# garden_logger.net
KiCad netlist of a schematic drawn in EAGLE
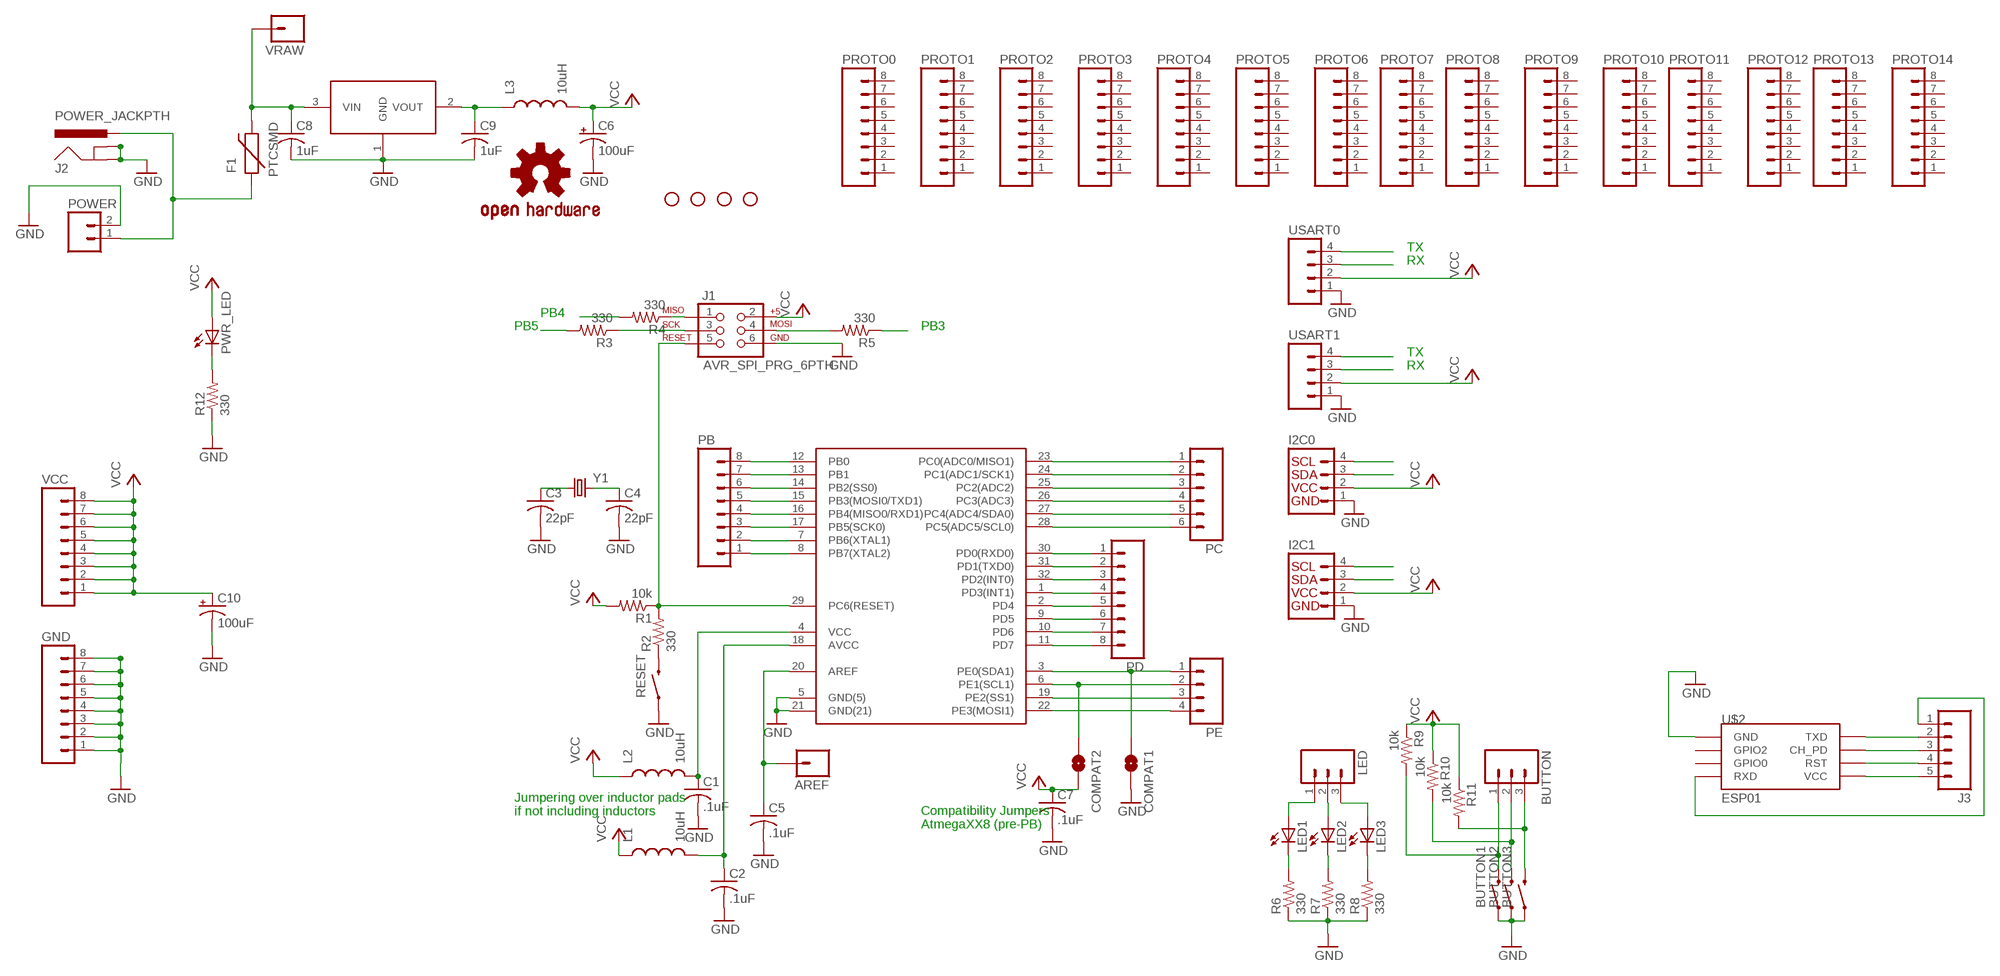
[diagram p0: schematic, sheet 1]

(export (version "E")
  (design (tool "Eeschema 10.0.6"))
  (components
    (comp (ref "AREF")
      (value "M01PTH")
      (footprint "eagle-import:1X01")
      (libsource (lib "eagle-import") (part "M01PTH"))
    )
    (comp (ref "BUTTON")
      (value "M03PTH")
      (footprint "eagle-import:1X03")
      (libsource (lib "eagle-import") (part "M03PTH"))
    )
    (comp (ref "BUTTON1")
      (value "SWITCH-MOMENTARY-2PTH")
      (footprint "eagle-import:TACTILE-PTH")
      (libsource (lib "eagle-import") (part "SWITCH-MOMENTARY-2PTH"))
    )
    (comp (ref "BUTTON2")
      (value "SWITCH-MOMENTARY-2PTH")
      (footprint "eagle-import:TACTILE-PTH")
      (libsource (lib "eagle-import") (part "SWITCH-MOMENTARY-2PTH"))
    )
    (comp (ref "BUTTON3")
      (value "SWITCH-MOMENTARY-2PTH")
      (footprint "eagle-import:TACTILE-PTH")
      (libsource (lib "eagle-import") (part "SWITCH-MOMENTARY-2PTH"))
    )
    (comp (ref "C1")
      (value ".1uF")
      (footprint "eagle-import:C0805")
      (libsource (lib "eagle-import") (part "C-USC0805"))
    )
    (comp (ref "C2")
      (value ".1uF")
      (footprint "eagle-import:C0805")
      (libsource (lib "eagle-import") (part "C-USC0805"))
    )
    (comp (ref "C3")
      (value "22pF")
      (footprint "eagle-import:C0805")
      (libsource (lib "eagle-import") (part "C-USC0805"))
    )
    (comp (ref "C4")
      (value "22pF")
      (footprint "eagle-import:C0805")
      (libsource (lib "eagle-import") (part "C-USC0805"))
    )
    (comp (ref "C5")
      (value ".1uF")
      (footprint "eagle-import:C0805")
      (libsource (lib "eagle-import") (part "C-USC0805"))
    )
    (comp (ref "C6")
      (value "100uF")
      (footprint "eagle-import:CPOL-RADIAL-100UF-25V")
      (libsource (lib "eagle-import") (part "CAP_POLPTH1"))
    )
    (comp (ref "C7")
      (value ".1uF")
      (footprint "eagle-import:C0805")
      (libsource (lib "eagle-import") (part "C-USC0805"))
    )
    (comp (ref "C8")
      (value "1uF")
      (footprint "eagle-import:C0805")
      (libsource (lib "eagle-import") (part "C-USC0805"))
    )
    (comp (ref "C9")
      (value "1uF")
      (footprint "eagle-import:C0805")
      (libsource (lib "eagle-import") (part "C-USC0805"))
    )
    (comp (ref "C10")
      (value "100uF")
      (footprint "eagle-import:CPOL-RADIAL-100UF-25V")
      (libsource (lib "eagle-import") (part "CAP_POLPTH1"))
    )
    (comp (ref "COMPAT1")
      (value "SOLDERJUMPER-OLDNO")
      (footprint "eagle-import:SJ_2S-NO")
      (libsource (lib "eagle-import") (part "SOLDERJUMPER-OLDNO"))
    )
    (comp (ref "COMPAT2")
      (value "SOLDERJUMPER-OLDNO")
      (footprint "eagle-import:SJ_2S-NO")
      (libsource (lib "eagle-import") (part "SOLDERJUMPER-OLDNO"))
    )
    (comp (ref "F1")
      (value "PTCSMD")
      (footprint "eagle-import:PTC-1206")
      (libsource (lib "eagle-import") (part "PTCSMD"))
    )
    (comp (ref "GND")
      (value "M08")
      (footprint "eagle-import:1X08_ROUND")
      (libsource (lib "eagle-import") (part "M08"))
    )
    (comp (ref "H1")
      (value "STAND-OFF")
      (footprint "eagle-import:STAND-OFF")
      (libsource (lib "eagle-import") (part "STAND-OFF"))
    )
    (comp (ref "H2")
      (value "STAND-OFF")
      (footprint "eagle-import:STAND-OFF")
      (libsource (lib "eagle-import") (part "STAND-OFF"))
    )
    (comp (ref "H3")
      (value "STAND-OFF")
      (footprint "eagle-import:STAND-OFF")
      (libsource (lib "eagle-import") (part "STAND-OFF"))
    )
    (comp (ref "H4")
      (value "STAND-OFF")
      (footprint "eagle-import:STAND-OFF")
      (libsource (lib "eagle-import") (part "STAND-OFF"))
    )
    (comp (ref "I2C0")
      (value "I2C_STANDARD")
      (footprint "eagle-import:1X04")
      (libsource (lib "eagle-import") (part "I2C_STANDARD"))
    )
    (comp (ref "I2C1")
      (value "I2C_STANDARD")
      (footprint "eagle-import:1X04")
      (libsource (lib "eagle-import") (part "I2C_STANDARD"))
    )
    (comp (ref "J1")
      (value "AVR_SPI_PRG_6PTH")
      (footprint "eagle-import:2X3")
      (libsource (lib "eagle-import") (part "AVR_SPI_PRG_6PTH"))
    )
    (comp (ref "J2")
      (value "POWER_JACKPTH")
      (footprint "eagle-import:POWER_JACK_PTH")
      (libsource (lib "eagle-import") (part "POWER_JACKPTH"))
    )
    (comp (ref "J3")
      (value "M05PTH")
      (footprint "eagle-import:1X05")
      (libsource (lib "eagle-import") (part "M05PTH"))
    )
    (comp (ref "L1")
      (value "10uH")
      (footprint "eagle-import:0805")
      (libsource (lib "eagle-import") (part "INDUCTOR0805"))
    )
    (comp (ref "L2")
      (value "10uH")
      (footprint "eagle-import:0805")
      (libsource (lib "eagle-import") (part "INDUCTOR0805"))
    )
    (comp (ref "L3")
      (value "10uH")
      (footprint "eagle-import:0805")
      (libsource (lib "eagle-import") (part "INDUCTOR0805"))
    )
    (comp (ref "LED")
      (value "M03PTH")
      (footprint "eagle-import:1X03")
      (libsource (lib "eagle-import") (part "M03PTH"))
    )
    (comp (ref "LED1")
      (value "LEDCHIPLED_0805")
      (footprint "eagle-import:CHIPLED_0805")
      (libsource (lib "eagle-import") (part "LEDCHIPLED_0805"))
    )
    (comp (ref "LED2")
      (value "LEDCHIPLED_0805")
      (footprint "eagle-import:CHIPLED_0805")
      (libsource (lib "eagle-import") (part "LEDCHIPLED_0805"))
    )
    (comp (ref "LED3")
      (value "LEDCHIPLED_0805")
      (footprint "eagle-import:CHIPLED_0805")
      (libsource (lib "eagle-import") (part "LEDCHIPLED_0805"))
    )
    (comp (ref "LOGO1")
      (value "OSHW-LOGOS")
      (footprint "eagle-import:OSHW-LOGO-S")
      (libsource (lib "eagle-import") (part "OSHW-LOGOS"))
    )
    (comp (ref "PB")
      (value "M08")
      (footprint "eagle-import:1X08_ROUND")
      (libsource (lib "eagle-import") (part "M08"))
    )
    (comp (ref "PC")
      (value "M06SILK_FEMALE_PTH")
      (footprint "eagle-import:1X06")
      (libsource (lib "eagle-import") (part "M06SILK_FEMALE_PTH"))
    )
    (comp (ref "PD")
      (value "M08")
      (footprint "eagle-import:1X08_ROUND")
      (libsource (lib "eagle-import") (part "M08"))
    )
    (comp (ref "PE")
      (value "M04PTH")
      (footprint "eagle-import:1X04")
      (libsource (lib "eagle-import") (part "M04PTH"))
    )
    (comp (ref "POWER")
      (value "M02PTH")
      (footprint "eagle-import:1X02")
      (libsource (lib "eagle-import") (part "M02PTH"))
    )
    (comp (ref "PROTO0")
      (value "M08")
      (footprint "eagle-import:1X08_ROUND")
      (libsource (lib "eagle-import") (part "M08"))
    )
    (comp (ref "PROTO1")
      (value "M08")
      (footprint "eagle-import:1X08_ROUND")
      (libsource (lib "eagle-import") (part "M08"))
    )
    (comp (ref "PROTO2")
      (value "M08")
      (footprint "eagle-import:1X08_ROUND")
      (libsource (lib "eagle-import") (part "M08"))
    )
    (comp (ref "PROTO3")
      (value "M08")
      (footprint "eagle-import:1X08_ROUND")
      (libsource (lib "eagle-import") (part "M08"))
    )
    (comp (ref "PROTO4")
      (value "M08")
      (footprint "eagle-import:1X08_ROUND")
      (libsource (lib "eagle-import") (part "M08"))
    )
    (comp (ref "PROTO5")
      (value "M08")
      (footprint "eagle-import:1X08_ROUND")
      (libsource (lib "eagle-import") (part "M08"))
    )
    (comp (ref "PROTO6")
      (value "M08")
      (footprint "eagle-import:1X08_ROUND")
      (libsource (lib "eagle-import") (part "M08"))
    )
    (comp (ref "PROTO7")
      (value "M08")
      (footprint "eagle-import:1X08_ROUND")
      (libsource (lib "eagle-import") (part "M08"))
    )
    (comp (ref "PROTO8")
      (value "M08")
      (footprint "eagle-import:1X08_ROUND")
      (libsource (lib "eagle-import") (part "M08"))
    )
    (comp (ref "PROTO9")
      (value "M08")
      (footprint "eagle-import:1X08_ROUND")
      (libsource (lib "eagle-import") (part "M08"))
    )
    (comp (ref "PROTO10")
      (value "M08")
      (footprint "eagle-import:1X08_ROUND")
      (libsource (lib "eagle-import") (part "M08"))
    )
    (comp (ref "PROTO11")
      (value "M08")
      (footprint "eagle-import:1X08_ROUND")
      (libsource (lib "eagle-import") (part "M08"))
    )
    (comp (ref "PROTO12")
      (value "M08")
      (footprint "eagle-import:1X08_ROUND")
      (libsource (lib "eagle-import") (part "M08"))
    )
    (comp (ref "PROTO13")
      (value "M08")
      (footprint "eagle-import:1X08_ROUND")
      (libsource (lib "eagle-import") (part "M08"))
    )
    (comp (ref "PROTO14")
      (value "M08")
      (footprint "eagle-import:1X08_ROUND")
      (libsource (lib "eagle-import") (part "M08"))
    )
    (comp (ref "PWR_LED")
      (value "LEDCHIPLED_0805")
      (footprint "eagle-import:CHIPLED_0805")
      (libsource (lib "eagle-import") (part "LEDCHIPLED_0805"))
    )
    (comp (ref "R1")
      (value "10k")
      (footprint "eagle-import:R0805")
      (libsource (lib "eagle-import") (part "R-US_R0805"))
    )
    (comp (ref "R2")
      (value "330")
      (footprint "eagle-import:R0805")
      (libsource (lib "eagle-import") (part "R-US_R0805"))
    )
    (comp (ref "R3")
      (value "330")
      (footprint "eagle-import:R0805")
      (libsource (lib "eagle-import") (part "R-US_R0805"))
    )
    (comp (ref "R4")
      (value "330")
      (footprint "eagle-import:R0805")
      (libsource (lib "eagle-import") (part "R-US_R0805"))
    )
    (comp (ref "R5")
      (value "330")
      (footprint "eagle-import:R0805")
      (libsource (lib "eagle-import") (part "R-US_R0805"))
    )
    (comp (ref "R6")
      (value "330")
      (footprint "eagle-import:R0805")
      (libsource (lib "eagle-import") (part "R-US_R0805"))
    )
    (comp (ref "R7")
      (value "330")
      (footprint "eagle-import:R0805")
      (libsource (lib "eagle-import") (part "R-US_R0805"))
    )
    (comp (ref "R8")
      (value "330")
      (footprint "eagle-import:R0805")
      (libsource (lib "eagle-import") (part "R-US_R0805"))
    )
    (comp (ref "R9")
      (value "10k")
      (footprint "eagle-import:R0805")
      (libsource (lib "eagle-import") (part "R-US_R0805"))
    )
    (comp (ref "R10")
      (value "10k")
      (footprint "eagle-import:R0805")
      (libsource (lib "eagle-import") (part "R-US_R0805"))
    )
    (comp (ref "R11")
      (value "10k")
      (footprint "eagle-import:R0805")
      (libsource (lib "eagle-import") (part "R-US_R0805"))
    )
    (comp (ref "R12")
      (value "330")
      (footprint "eagle-import:R0805")
      (libsource (lib "eagle-import") (part "R-US_R0805"))
    )
    (comp (ref "RESET")
      (value "SWITCH-MOMENTARY-2PTH")
      (footprint "eagle-import:TACTILE-PTH")
      (libsource (lib "eagle-import") (part "SWITCH-MOMENTARY-2PTH"))
    )
    (comp (ref "U$1")
      (value "ATMEGA328PB_TQFP")
      (footprint "eagle-import:TQFP32-08")
      (libsource (lib "eagle-import") (part "ATMEGA328PB_TQFP"))
    )
    (comp (ref "U$2")
      (value "ESP01")
      (footprint "eagle-import:ESP01")
      (libsource (lib "eagle-import") (part "ESP01"))
    )
    (comp (ref "U$3")
      (value "MCP1702")
      (footprint "eagle-import:SOT23-3")
      (libsource (lib "eagle-import") (part "MCP1702"))
    )
    (comp (ref "USART0")
      (value "M04PTH")
      (footprint "eagle-import:1X04")
      (libsource (lib "eagle-import") (part "M04PTH"))
    )
    (comp (ref "USART1")
      (value "M04PTH")
      (footprint "eagle-import:1X04")
      (libsource (lib "eagle-import") (part "M04PTH"))
    )
    (comp (ref "VCC")
      (value "M08")
      (footprint "eagle-import:1X08_ROUND")
      (libsource (lib "eagle-import") (part "M08"))
    )
    (comp (ref "VRAW")
      (value "M01PTH")
      (footprint "eagle-import:1X01")
      (libsource (lib "eagle-import") (part "M01PTH"))
    )
    (comp (ref "Y1")
      (value "CRYSTALHC49US")
      (footprint "eagle-import:HC49US")
      (libsource (lib "eagle-import") (part "CRYSTALHC49US"))
    )
  )
  (nets
    (net (code "1") (name "/PB3") (class "Default")
      (node (ref "PB") (pin "5") (pinfunction "5_5") (pintype "passive"))
      (node (ref "R5") (pin "1") (pinfunction "1_1") (pintype "passive"))
      (node (ref "U$1") (pin "15") (pinfunction "PB3(MOSI0/TXD1)_15") (pintype "bidirectional"))
      (node (ref "USART1") (pin "4") (pinfunction "4_4") (pintype "passive"))
    )
    (net (code "2") (name "/PB4") (class "Default")
      (node (ref "PB") (pin "4") (pinfunction "4_4") (pintype "passive"))
      (node (ref "R4") (pin "2") (pinfunction "2_2") (pintype "passive"))
      (node (ref "U$1") (pin "16") (pinfunction "PB4(MISO0/RXD1)_16") (pintype "bidirectional"))
      (node (ref "USART1") (pin "3") (pinfunction "3_3") (pintype "passive"))
    )
    (net (code "3") (name "/PB5") (class "Default")
      (node (ref "PB") (pin "3") (pinfunction "3_3") (pintype "passive"))
      (node (ref "R3") (pin "2") (pinfunction "2_2") (pintype "passive"))
      (node (ref "U$1") (pin "17") (pinfunction "PB5(SCK0)_17") (pintype "bidirectional"))
    )
    (net (code "4") (name "/PB6") (class "Default")
      (node (ref "C3") (pin "1") (pinfunction "1_1") (pintype "passive"))
      (node (ref "PB") (pin "2") (pinfunction "2_2") (pintype "passive"))
      (node (ref "U$1") (pin "7") (pinfunction "PB6(XTAL1)_7") (pintype "bidirectional"))
      (node (ref "Y1") (pin "1") (pinfunction "1_1") (pintype "passive"))
    )
    (net (code "5") (name "/PB7") (class "Default")
      (node (ref "C4") (pin "1") (pinfunction "1_1") (pintype "passive"))
      (node (ref "PB") (pin "1") (pinfunction "1_1") (pintype "passive"))
      (node (ref "U$1") (pin "8") (pinfunction "PB7(XTAL2)_8") (pintype "bidirectional"))
      (node (ref "Y1") (pin "2") (pinfunction "2_2") (pintype "passive"))
    )
    (net (code "6") (name "/PC4") (class "Default")
      (node (ref "I2C0") (pin "3") (pinfunction "3_3") (pintype "passive"))
      (node (ref "PC") (pin "5") (pinfunction "5_5") (pintype "passive"))
      (node (ref "U$1") (pin "27") (pinfunction "PC4(ADC4/SDA0)_27") (pintype "bidirectional"))
    )
    (net (code "7") (name "/PC5") (class "Default")
      (node (ref "I2C0") (pin "4") (pinfunction "4_4") (pintype "passive"))
      (node (ref "PC") (pin "6") (pinfunction "6_6") (pintype "passive"))
      (node (ref "U$1") (pin "28") (pinfunction "PC5(ADC5/SCL0)_28") (pintype "bidirectional"))
    )
    (net (code "8") (name "/PD0") (class "Default")
      (node (ref "PD") (pin "1") (pinfunction "1_1") (pintype "passive"))
      (node (ref "U$1") (pin "30") (pinfunction "PD0(RXD0)_30") (pintype "bidirectional"))
      (node (ref "USART0") (pin "3") (pinfunction "3_3") (pintype "passive"))
    )
    (net (code "9") (name "/PD1") (class "Default")
      (node (ref "PD") (pin "2") (pinfunction "2_2") (pintype "passive"))
      (node (ref "U$1") (pin "31") (pinfunction "PD1(TXD0)_31") (pintype "bidirectional"))
      (node (ref "USART0") (pin "4") (pinfunction "4_4") (pintype "passive"))
    )
    (net (code "10") (name "/PE0") (class "Default")
      (node (ref "COMPAT1") (pin "1") (pinfunction "1_1") (pintype "passive"))
      (node (ref "I2C1") (pin "3") (pinfunction "3_3") (pintype "passive"))
      (node (ref "PE") (pin "1") (pinfunction "1_1") (pintype "passive"))
      (node (ref "U$1") (pin "3") (pinfunction "PE0(SDA1)_3") (pintype "bidirectional"))
    )
    (net (code "11") (name "/PE1") (class "Default")
      (node (ref "COMPAT2") (pin "1") (pinfunction "1_1") (pintype "passive"))
      (node (ref "I2C1") (pin "4") (pinfunction "4_4") (pintype "passive"))
      (node (ref "PE") (pin "2") (pinfunction "2_2") (pintype "passive"))
      (node (ref "U$1") (pin "6") (pinfunction "PE1(SCL1)_6") (pintype "bidirectional"))
    )
    (net (code "12") (name "GND") (class "Default")
      (node (ref "BUTTON1") (pin "1") (pinfunction "1_1") (pintype "passive"))
      (node (ref "BUTTON2") (pin "1") (pinfunction "1_1") (pintype "passive"))
      (node (ref "BUTTON3") (pin "1") (pinfunction "1_1") (pintype "passive"))
      (node (ref "C1") (pin "2") (pinfunction "2_2") (pintype "passive"))
      (node (ref "C10") (pin "2") (pinfunction "-_2") (pintype "passive"))
      (node (ref "C2") (pin "2") (pinfunction "2_2") (pintype "passive"))
      (node (ref "C3") (pin "2") (pinfunction "2_2") (pintype "passive"))
      (node (ref "C4") (pin "2") (pinfunction "2_2") (pintype "passive"))
      (node (ref "C5") (pin "2") (pinfunction "2_2") (pintype "passive"))
      (node (ref "C6") (pin "2") (pinfunction "-_2") (pintype "passive"))
      (node (ref "C7") (pin "2") (pinfunction "2_2") (pintype "passive"))
      (node (ref "C8") (pin "2") (pinfunction "2_2") (pintype "passive"))
      (node (ref "C9") (pin "2") (pinfunction "2_2") (pintype "passive"))
      (node (ref "COMPAT1") (pin "2") (pinfunction "2_2") (pintype "passive"))
      (node (ref "GND") (pin "1") (pinfunction "1_1") (pintype "passive"))
      (node (ref "GND") (pin "2") (pinfunction "2_2") (pintype "passive"))
      (node (ref "GND") (pin "3") (pinfunction "3_3") (pintype "passive"))
      (node (ref "GND") (pin "4") (pinfunction "4_4") (pintype "passive"))
      (node (ref "GND") (pin "5") (pinfunction "5_5") (pintype "passive"))
      (node (ref "GND") (pin "6") (pinfunction "6_6") (pintype "passive"))
      (node (ref "GND") (pin "7") (pinfunction "7_7") (pintype "passive"))
      (node (ref "GND") (pin "8") (pinfunction "8_8") (pintype "passive"))
      (node (ref "I2C0") (pin "1") (pinfunction "1_1") (pintype "passive"))
      (node (ref "I2C1") (pin "1") (pinfunction "1_1") (pintype "passive"))
      (node (ref "J1") (pin "6") (pinfunction "6_6") (pintype "passive"))
      (node (ref "J2") (pin "GND") (pinfunction "GND_GND") (pintype "bidirectional"))
      (node (ref "J2") (pin "GNDBREAK") (pinfunction "GNDBREAK_GNDBREAK") (pintype "bidirectional"))
      (node (ref "POWER") (pin "2") (pinfunction "2_2") (pintype "passive"))
      (node (ref "R12") (pin "1") (pinfunction "1_1") (pintype "passive"))
      (node (ref "R6") (pin "1") (pinfunction "1_1") (pintype "passive"))
      (node (ref "R7") (pin "1") (pinfunction "1_1") (pintype "passive"))
      (node (ref "R8") (pin "1") (pinfunction "1_1") (pintype "passive"))
      (node (ref "RESET") (pin "1") (pinfunction "1_1") (pintype "passive"))
      (node (ref "U$1") (pin "21") (pinfunction "GND(21)_21") (pintype "power_in"))
      (node (ref "U$1") (pin "5") (pinfunction "GND(5)_5") (pintype "power_in"))
      (node (ref "U$2") (pin "GND") (pinfunction "GND_GND") (pintype "bidirectional"))
      (node (ref "U$3") (pin "1") (pinfunction "GND_1") (pintype "bidirectional"))
      (node (ref "USART0") (pin "1") (pinfunction "1_1") (pintype "passive"))
      (node (ref "USART1") (pin "1") (pinfunction "1_1") (pintype "passive"))
    )
    (net (code "13") (name "Net-(BUTTON1-2)") (class "Default")
      (node (ref "BUTTON") (pin "1") (pinfunction "1_1") (pintype "passive"))
      (node (ref "BUTTON1") (pin "3") (pinfunction "2_3") (pintype "passive"))
      (node (ref "R9") (pin "2") (pinfunction "2_2") (pintype "passive"))
    )
    (net (code "14") (name "Net-(BUTTON2-2)") (class "Default")
      (node (ref "BUTTON") (pin "2") (pinfunction "2_2") (pintype "passive"))
      (node (ref "BUTTON2") (pin "3") (pinfunction "2_3") (pintype "passive"))
      (node (ref "R10") (pin "2") (pinfunction "2_2") (pintype "passive"))
    )
    (net (code "15") (name "Net-(BUTTON3-2)") (class "Default")
      (node (ref "BUTTON") (pin "3") (pinfunction "3_3") (pintype "passive"))
      (node (ref "BUTTON3") (pin "3") (pinfunction "2_3") (pintype "passive"))
      (node (ref "R11") (pin "2") (pinfunction "2_2") (pintype "passive"))
    )
    (net (code "16") (name "Net-(F1-Pad1)") (class "Default")
      (node (ref "F1") (pin "1") (pinfunction "1_1") (pintype "bidirectional"))
      (node (ref "J2") (pin "PWR") (pinfunction "PWR_PWR") (pintype "bidirectional"))
      (node (ref "POWER") (pin "1") (pinfunction "1_1") (pintype "passive"))
    )
    (net (code "17") (name "Net-(J1-Pad1)") (class "Default")
      (node (ref "J1") (pin "1") (pinfunction "1_1") (pintype "passive"))
      (node (ref "R4") (pin "1") (pinfunction "1_1") (pintype "passive"))
    )
    (net (code "18") (name "Net-(J1-Pad3)") (class "Default")
      (node (ref "J1") (pin "3") (pinfunction "3_3") (pintype "passive"))
      (node (ref "R3") (pin "1") (pinfunction "1_1") (pintype "passive"))
    )
    (net (code "19") (name "Net-(J1-Pad4)") (class "Default")
      (node (ref "J1") (pin "4") (pinfunction "4_4") (pintype "passive"))
      (node (ref "R5") (pin "2") (pinfunction "2_2") (pintype "passive"))
    )
    (net (code "20") (name "Net-(J3-Pad3)") (class "Default")
      (node (ref "J3") (pin "3") (pinfunction "3_3") (pintype "passive"))
      (node (ref "U$2") (pin "CH_PD") (pinfunction "CH_PD_CH_PD") (pintype "bidirectional"))
    )
    (net (code "21") (name "Net-(J3-Pad4)") (class "Default")
      (node (ref "J3") (pin "4") (pinfunction "4_4") (pintype "passive"))
      (node (ref "U$2") (pin "RST") (pinfunction "RST_RST") (pintype "bidirectional"))
    )
    (net (code "22") (name "Net-(J3-Pad5)") (class "Default")
      (node (ref "J3") (pin "5") (pinfunction "5_5") (pintype "passive"))
      (node (ref "U$2") (pin "VCC") (pinfunction "VCC_VCC") (pintype "bidirectional"))
    )
    (net (code "23") (name "Net-(LED-Pad1)") (class "Default")
      (node (ref "LED") (pin "1") (pinfunction "1_1") (pintype "passive"))
      (node (ref "LED1") (pin "A") (pinfunction "A_A") (pintype "passive"))
    )
    (net (code "24") (name "Net-(LED-Pad2)") (class "Default")
      (node (ref "LED") (pin "2") (pinfunction "2_2") (pintype "passive"))
      (node (ref "LED2") (pin "A") (pinfunction "A_A") (pintype "passive"))
    )
    (net (code "25") (name "Net-(LED-Pad3)") (class "Default")
      (node (ref "LED") (pin "3") (pinfunction "3_3") (pintype "passive"))
      (node (ref "LED3") (pin "A") (pinfunction "A_A") (pintype "passive"))
    )
    (net (code "26") (name "Net-(LED1-PadC)") (class "Default")
      (node (ref "LED1") (pin "C") (pinfunction "C_C") (pintype "passive"))
      (node (ref "R6") (pin "2") (pinfunction "2_2") (pintype "passive"))
    )
    (net (code "27") (name "Net-(LED2-PadC)") (class "Default")
      (node (ref "LED2") (pin "C") (pinfunction "C_C") (pintype "passive"))
      (node (ref "R7") (pin "2") (pinfunction "2_2") (pintype "passive"))
    )
    (net (code "28") (name "Net-(LED3-PadC)") (class "Default")
      (node (ref "LED3") (pin "C") (pinfunction "C_C") (pintype "passive"))
      (node (ref "R8") (pin "2") (pinfunction "2_2") (pintype "passive"))
    )
    (net (code "29") (name "Net-(PWR_LED-PadC)") (class "Default")
      (node (ref "PWR_LED") (pin "C") (pinfunction "C_C") (pintype "passive"))
      (node (ref "R12") (pin "2") (pinfunction "2_2") (pintype "passive"))
    )
    (net (code "30") (name "Net-(RESET-2)") (class "Default")
      (node (ref "R2") (pin "1") (pinfunction "1_1") (pintype "passive"))
      (node (ref "RESET") (pin "3") (pinfunction "2_3") (pintype "passive"))
    )
    (net (code "31") (name "Net-(U$1-AREF)") (class "Default")
      (node (ref "AREF") (pin "1") (pinfunction "1_1") (pintype "passive"))
      (node (ref "C5") (pin "1") (pinfunction "1_1") (pintype "passive"))
      (node (ref "U$1") (pin "20") (pinfunction "AREF_20") (pintype "bidirectional"))
    )
    (net (code "32") (name "Net-(U$1-AVCC)") (class "Default")
      (node (ref "C2") (pin "1") (pinfunction "1_1") (pintype "passive"))
      (node (ref "L1") (pin "2") (pinfunction "2_2") (pintype "passive"))
      (node (ref "U$1") (pin "18") (pinfunction "AVCC_18") (pintype "power_in"))
    )
    (net (code "33") (name "Net-(U$1-PB0)") (class "Default")
      (node (ref "PB") (pin "8") (pinfunction "8_8") (pintype "passive"))
      (node (ref "U$1") (pin "12") (pinfunction "PB0_12") (pintype "bidirectional"))
    )
    (net (code "34") (name "Net-(U$1-PB1)") (class "Default")
      (node (ref "PB") (pin "7") (pinfunction "7_7") (pintype "passive"))
      (node (ref "U$1") (pin "13") (pinfunction "PB1_13") (pintype "bidirectional"))
    )
    (net (code "35") (name "Net-(U$1-PB2(SS0))") (class "Default")
      (node (ref "PB") (pin "6") (pinfunction "6_6") (pintype "passive"))
      (node (ref "U$1") (pin "14") (pinfunction "PB2(SS0)_14") (pintype "bidirectional"))
    )
    (net (code "36") (name "Net-(U$1-PC0(ADC0{slash}MISO1))") (class "Default")
      (node (ref "PC") (pin "1") (pinfunction "1_1") (pintype "passive"))
      (node (ref "U$1") (pin "23") (pinfunction "PC0(ADC0/MISO1)_23") (pintype "bidirectional"))
    )
    (net (code "37") (name "Net-(U$1-PC1(ADC1{slash}SCK1))") (class "Default")
      (node (ref "PC") (pin "2") (pinfunction "2_2") (pintype "passive"))
      (node (ref "U$1") (pin "24") (pinfunction "PC1(ADC1/SCK1)_24") (pintype "bidirectional"))
    )
    (net (code "38") (name "Net-(U$1-PC2(ADC2))") (class "Default")
      (node (ref "PC") (pin "3") (pinfunction "3_3") (pintype "passive"))
      (node (ref "U$1") (pin "25") (pinfunction "PC2(ADC2)_25") (pintype "bidirectional"))
    )
    (net (code "39") (name "Net-(U$1-PC3(ADC3))") (class "Default")
      (node (ref "PC") (pin "4") (pinfunction "4_4") (pintype "passive"))
      (node (ref "U$1") (pin "26") (pinfunction "PC3(ADC3)_26") (pintype "bidirectional"))
    )
    (net (code "40") (name "Net-(U$1-PC6(RESET))") (class "Default")
      (node (ref "J1") (pin "5") (pinfunction "5_5") (pintype "passive"))
      (node (ref "R1") (pin "1") (pinfunction "1_1") (pintype "passive"))
      (node (ref "R2") (pin "2") (pinfunction "2_2") (pintype "passive"))
      (node (ref "U$1") (pin "29") (pinfunction "PC6(RESET)_29") (pintype "bidirectional"))
    )
    (net (code "41") (name "Net-(U$1-PD2(INT0))") (class "Default")
      (node (ref "PD") (pin "3") (pinfunction "3_3") (pintype "passive"))
      (node (ref "U$1") (pin "32") (pinfunction "PD2(INT0)_32") (pintype "bidirectional"))
    )
    (net (code "42") (name "Net-(U$1-PD3(INT1))") (class "Default")
      (node (ref "PD") (pin "4") (pinfunction "4_4") (pintype "passive"))
      (node (ref "U$1") (pin "1") (pinfunction "PD3(INT1)_1") (pintype "bidirectional"))
    )
    (net (code "43") (name "Net-(U$1-PD4)") (class "Default")
      (node (ref "PD") (pin "5") (pinfunction "5_5") (pintype "passive"))
      (node (ref "U$1") (pin "2") (pinfunction "PD4_2") (pintype "bidirectional"))
    )
    (net (code "44") (name "Net-(U$1-PD5)") (class "Default")
      (node (ref "PD") (pin "6") (pinfunction "6_6") (pintype "passive"))
      (node (ref "U$1") (pin "9") (pinfunction "PD5_9") (pintype "bidirectional"))
    )
    (net (code "45") (name "Net-(U$1-PD6)") (class "Default")
      (node (ref "PD") (pin "7") (pinfunction "7_7") (pintype "passive"))
      (node (ref "U$1") (pin "10") (pinfunction "PD6_10") (pintype "bidirectional"))
    )
    (net (code "46") (name "Net-(U$1-PD7)") (class "Default")
      (node (ref "PD") (pin "8") (pinfunction "8_8") (pintype "passive"))
      (node (ref "U$1") (pin "11") (pinfunction "PD7_11") (pintype "bidirectional"))
    )
    (net (code "47") (name "Net-(U$1-PE2(SS1))") (class "Default")
      (node (ref "PE") (pin "3") (pinfunction "3_3") (pintype "passive"))
      (node (ref "U$1") (pin "19") (pinfunction "PE2(SS1)_19") (pintype "bidirectional"))
    )
    (net (code "48") (name "Net-(U$1-PE3(MOSI1))") (class "Default")
      (node (ref "PE") (pin "4") (pinfunction "4_4") (pintype "passive"))
      (node (ref "U$1") (pin "22") (pinfunction "PE3(MOSI1)_22") (pintype "bidirectional"))
    )
    (net (code "49") (name "Net-(U$1-VCC)") (class "Default")
      (node (ref "C1") (pin "1") (pinfunction "1_1") (pintype "passive"))
      (node (ref "L2") (pin "2") (pinfunction "2_2") (pintype "passive"))
      (node (ref "U$1") (pin "4") (pinfunction "VCC_4") (pintype "power_in"))
    )
    (net (code "50") (name "Net-(U$2-RXD)") (class "Default")
      (node (ref "J3") (pin "1") (pinfunction "1_1") (pintype "passive"))
      (node (ref "U$2") (pin "RX") (pinfunction "RXD_RX") (pintype "bidirectional"))
    )
    (net (code "51") (name "Net-(U$2-TXD)") (class "Default")
      (node (ref "J3") (pin "2") (pinfunction "2_2") (pintype "passive"))
      (node (ref "U$2") (pin "TX") (pinfunction "TXD_TX") (pintype "bidirectional"))
    )
    (net (code "52") (name "Net-(U$3-VIN)") (class "Default")
      (node (ref "C8") (pin "1") (pinfunction "1_1") (pintype "passive"))
      (node (ref "F1") (pin "2") (pinfunction "2_2") (pintype "bidirectional"))
      (node (ref "U$3") (pin "3") (pinfunction "VIN_3") (pintype "bidirectional"))
      (node (ref "VRAW") (pin "1") (pinfunction "1_1") (pintype "passive"))
    )
    (net (code "53") (name "Net-(U$3-VOUT)") (class "Default")
      (node (ref "C9") (pin "1") (pinfunction "1_1") (pintype "passive"))
      (node (ref "L3") (pin "1") (pinfunction "1_1") (pintype "passive"))
      (node (ref "U$3") (pin "2") (pinfunction "VOUT_2") (pintype "bidirectional"))
    )
    (net (code "54") (name "VCC") (class "Default")
      (node (ref "C10") (pin "1") (pinfunction "+_1") (pintype "passive"))
      (node (ref "C6") (pin "1") (pinfunction "+_1") (pintype "passive"))
      (node (ref "C7") (pin "1") (pinfunction "1_1") (pintype "passive"))
      (node (ref "COMPAT2") (pin "2") (pinfunction "2_2") (pintype "passive"))
      (node (ref "I2C0") (pin "2") (pinfunction "2_2") (pintype "passive"))
      (node (ref "I2C1") (pin "2") (pinfunction "2_2") (pintype "passive"))
      (node (ref "J1") (pin "2") (pinfunction "2_2") (pintype "passive"))
      (node (ref "L1") (pin "1") (pinfunction "1_1") (pintype "passive"))
      (node (ref "L2") (pin "1") (pinfunction "1_1") (pintype "passive"))
      (node (ref "L3") (pin "2") (pinfunction "2_2") (pintype "passive"))
      (node (ref "PWR_LED") (pin "A") (pinfunction "A_A") (pintype "passive"))
      (node (ref "R1") (pin "2") (pinfunction "2_2") (pintype "passive"))
      (node (ref "R10") (pin "1") (pinfunction "1_1") (pintype "passive"))
      (node (ref "R11") (pin "1") (pinfunction "1_1") (pintype "passive"))
      (node (ref "R9") (pin "1") (pinfunction "1_1") (pintype "passive"))
      (node (ref "USART0") (pin "2") (pinfunction "2_2") (pintype "passive"))
      (node (ref "USART1") (pin "2") (pinfunction "2_2") (pintype "passive"))
      (node (ref "VCC") (pin "1") (pinfunction "1_1") (pintype "passive"))
      (node (ref "VCC") (pin "2") (pinfunction "2_2") (pintype "passive"))
      (node (ref "VCC") (pin "3") (pinfunction "3_3") (pintype "passive"))
      (node (ref "VCC") (pin "4") (pinfunction "4_4") (pintype "passive"))
      (node (ref "VCC") (pin "5") (pinfunction "5_5") (pintype "passive"))
      (node (ref "VCC") (pin "6") (pinfunction "6_6") (pintype "passive"))
      (node (ref "VCC") (pin "7") (pinfunction "7_7") (pintype "passive"))
      (node (ref "VCC") (pin "8") (pinfunction "8_8") (pintype "passive"))
    )
    (net (code "55") (name "unconnected-(PROTO0-Pad1)") (class "Default")
      (node (ref "PROTO0") (pin "1") (pinfunction "1_1") (pintype "passive"))
    )
    (net (code "56") (name "unconnected-(PROTO0-Pad2)") (class "Default")
      (node (ref "PROTO0") (pin "2") (pinfunction "2_2") (pintype "passive"))
    )
    (net (code "57") (name "unconnected-(PROTO0-Pad3)") (class "Default")
      (node (ref "PROTO0") (pin "3") (pinfunction "3_3") (pintype "passive"))
    )
    (net (code "58") (name "unconnected-(PROTO0-Pad4)") (class "Default")
      (node (ref "PROTO0") (pin "4") (pinfunction "4_4") (pintype "passive"))
    )
    (net (code "59") (name "unconnected-(PROTO0-Pad5)") (class "Default")
      (node (ref "PROTO0") (pin "5") (pinfunction "5_5") (pintype "passive"))
    )
    (net (code "60") (name "unconnected-(PROTO0-Pad6)") (class "Default")
      (node (ref "PROTO0") (pin "6") (pinfunction "6_6") (pintype "passive"))
    )
    (net (code "61") (name "unconnected-(PROTO0-Pad7)") (class "Default")
      (node (ref "PROTO0") (pin "7") (pinfunction "7_7") (pintype "passive"))
    )
    (net (code "62") (name "unconnected-(PROTO0-Pad8)") (class "Default")
      (node (ref "PROTO0") (pin "8") (pinfunction "8_8") (pintype "passive"))
    )
    (net (code "63") (name "unconnected-(PROTO1-Pad1)") (class "Default")
      (node (ref "PROTO1") (pin "1") (pinfunction "1_1") (pintype "passive"))
    )
    (net (code "64") (name "unconnected-(PROTO1-Pad2)") (class "Default")
      (node (ref "PROTO1") (pin "2") (pinfunction "2_2") (pintype "passive"))
    )
    (net (code "65") (name "unconnected-(PROTO1-Pad3)") (class "Default")
      (node (ref "PROTO1") (pin "3") (pinfunction "3_3") (pintype "passive"))
    )
    (net (code "66") (name "unconnected-(PROTO1-Pad4)") (class "Default")
      (node (ref "PROTO1") (pin "4") (pinfunction "4_4") (pintype "passive"))
    )
    (net (code "67") (name "unconnected-(PROTO1-Pad5)") (class "Default")
      (node (ref "PROTO1") (pin "5") (pinfunction "5_5") (pintype "passive"))
    )
    (net (code "68") (name "unconnected-(PROTO1-Pad6)") (class "Default")
      (node (ref "PROTO1") (pin "6") (pinfunction "6_6") (pintype "passive"))
    )
    (net (code "69") (name "unconnected-(PROTO1-Pad7)") (class "Default")
      (node (ref "PROTO1") (pin "7") (pinfunction "7_7") (pintype "passive"))
    )
    (net (code "70") (name "unconnected-(PROTO1-Pad8)") (class "Default")
      (node (ref "PROTO1") (pin "8") (pinfunction "8_8") (pintype "passive"))
    )
    (net (code "71") (name "unconnected-(PROTO2-Pad1)") (class "Default")
      (node (ref "PROTO2") (pin "1") (pinfunction "1_1") (pintype "passive"))
    )
    (net (code "72") (name "unconnected-(PROTO2-Pad2)") (class "Default")
      (node (ref "PROTO2") (pin "2") (pinfunction "2_2") (pintype "passive"))
    )
    (net (code "73") (name "unconnected-(PROTO2-Pad3)") (class "Default")
      (node (ref "PROTO2") (pin "3") (pinfunction "3_3") (pintype "passive"))
    )
    (net (code "74") (name "unconnected-(PROTO2-Pad4)") (class "Default")
      (node (ref "PROTO2") (pin "4") (pinfunction "4_4") (pintype "passive"))
    )
    (net (code "75") (name "unconnected-(PROTO2-Pad5)") (class "Default")
      (node (ref "PROTO2") (pin "5") (pinfunction "5_5") (pintype "passive"))
    )
    (net (code "76") (name "unconnected-(PROTO2-Pad6)") (class "Default")
      (node (ref "PROTO2") (pin "6") (pinfunction "6_6") (pintype "passive"))
    )
    (net (code "77") (name "unconnected-(PROTO2-Pad7)") (class "Default")
      (node (ref "PROTO2") (pin "7") (pinfunction "7_7") (pintype "passive"))
    )
    (net (code "78") (name "unconnected-(PROTO2-Pad8)") (class "Default")
      (node (ref "PROTO2") (pin "8") (pinfunction "8_8") (pintype "passive"))
    )
    (net (code "79") (name "unconnected-(PROTO3-Pad1)") (class "Default")
      (node (ref "PROTO3") (pin "1") (pinfunction "1_1") (pintype "passive"))
    )
    (net (code "80") (name "unconnected-(PROTO3-Pad2)") (class "Default")
      (node (ref "PROTO3") (pin "2") (pinfunction "2_2") (pintype "passive"))
    )
    (net (code "81") (name "unconnected-(PROTO3-Pad3)") (class "Default")
      (node (ref "PROTO3") (pin "3") (pinfunction "3_3") (pintype "passive"))
    )
    (net (code "82") (name "unconnected-(PROTO3-Pad4)") (class "Default")
      (node (ref "PROTO3") (pin "4") (pinfunction "4_4") (pintype "passive"))
    )
    (net (code "83") (name "unconnected-(PROTO3-Pad5)") (class "Default")
      (node (ref "PROTO3") (pin "5") (pinfunction "5_5") (pintype "passive"))
    )
    (net (code "84") (name "unconnected-(PROTO3-Pad6)") (class "Default")
      (node (ref "PROTO3") (pin "6") (pinfunction "6_6") (pintype "passive"))
    )
    (net (code "85") (name "unconnected-(PROTO3-Pad7)") (class "Default")
      (node (ref "PROTO3") (pin "7") (pinfunction "7_7") (pintype "passive"))
    )
    (net (code "86") (name "unconnected-(PROTO3-Pad8)") (class "Default")
      (node (ref "PROTO3") (pin "8") (pinfunction "8_8") (pintype "passive"))
    )
    (net (code "87") (name "unconnected-(PROTO4-Pad1)") (class "Default")
      (node (ref "PROTO4") (pin "1") (pinfunction "1_1") (pintype "passive"))
    )
    (net (code "88") (name "unconnected-(PROTO4-Pad2)") (class "Default")
      (node (ref "PROTO4") (pin "2") (pinfunction "2_2") (pintype "passive"))
    )
    (net (code "89") (name "unconnected-(PROTO4-Pad3)") (class "Default")
      (node (ref "PROTO4") (pin "3") (pinfunction "3_3") (pintype "passive"))
    )
    (net (code "90") (name "unconnected-(PROTO4-Pad4)") (class "Default")
      (node (ref "PROTO4") (pin "4") (pinfunction "4_4") (pintype "passive"))
    )
    (net (code "91") (name "unconnected-(PROTO4-Pad5)") (class "Default")
      (node (ref "PROTO4") (pin "5") (pinfunction "5_5") (pintype "passive"))
    )
    (net (code "92") (name "unconnected-(PROTO4-Pad6)") (class "Default")
      (node (ref "PROTO4") (pin "6") (pinfunction "6_6") (pintype "passive"))
    )
    (net (code "93") (name "unconnected-(PROTO4-Pad7)") (class "Default")
      (node (ref "PROTO4") (pin "7") (pinfunction "7_7") (pintype "passive"))
    )
    (net (code "94") (name "unconnected-(PROTO4-Pad8)") (class "Default")
      (node (ref "PROTO4") (pin "8") (pinfunction "8_8") (pintype "passive"))
    )
    (net (code "95") (name "unconnected-(PROTO5-Pad1)") (class "Default")
      (node (ref "PROTO5") (pin "1") (pinfunction "1_1") (pintype "passive"))
    )
    (net (code "96") (name "unconnected-(PROTO5-Pad2)") (class "Default")
      (node (ref "PROTO5") (pin "2") (pinfunction "2_2") (pintype "passive"))
    )
    (net (code "97") (name "unconnected-(PROTO5-Pad3)") (class "Default")
      (node (ref "PROTO5") (pin "3") (pinfunction "3_3") (pintype "passive"))
    )
    (net (code "98") (name "unconnected-(PROTO5-Pad4)") (class "Default")
      (node (ref "PROTO5") (pin "4") (pinfunction "4_4") (pintype "passive"))
    )
    (net (code "99") (name "unconnected-(PROTO5-Pad5)") (class "Default")
      (node (ref "PROTO5") (pin "5") (pinfunction "5_5") (pintype "passive"))
    )
    (net (code "100") (name "unconnected-(PROTO5-Pad6)") (class "Default")
      (node (ref "PROTO5") (pin "6") (pinfunction "6_6") (pintype "passive"))
    )
    (net (code "101") (name "unconnected-(PROTO5-Pad7)") (class "Default")
      (node (ref "PROTO5") (pin "7") (pinfunction "7_7") (pintype "passive"))
    )
    (net (code "102") (name "unconnected-(PROTO5-Pad8)") (class "Default")
      (node (ref "PROTO5") (pin "8") (pinfunction "8_8") (pintype "passive"))
    )
    (net (code "103") (name "unconnected-(PROTO6-Pad1)") (class "Default")
      (node (ref "PROTO6") (pin "1") (pinfunction "1_1") (pintype "passive"))
    )
    (net (code "104") (name "unconnected-(PROTO6-Pad2)") (class "Default")
      (node (ref "PROTO6") (pin "2") (pinfunction "2_2") (pintype "passive"))
    )
    (net (code "105") (name "unconnected-(PROTO6-Pad3)") (class "Default")
      (node (ref "PROTO6") (pin "3") (pinfunction "3_3") (pintype "passive"))
    )
    (net (code "106") (name "unconnected-(PROTO6-Pad4)") (class "Default")
      (node (ref "PROTO6") (pin "4") (pinfunction "4_4") (pintype "passive"))
    )
    (net (code "107") (name "unconnected-(PROTO6-Pad5)") (class "Default")
      (node (ref "PROTO6") (pin "5") (pinfunction "5_5") (pintype "passive"))
    )
    (net (code "108") (name "unconnected-(PROTO6-Pad6)") (class "Default")
      (node (ref "PROTO6") (pin "6") (pinfunction "6_6") (pintype "passive"))
    )
    (net (code "109") (name "unconnected-(PROTO6-Pad7)") (class "Default")
      (node (ref "PROTO6") (pin "7") (pinfunction "7_7") (pintype "passive"))
    )
    (net (code "110") (name "unconnected-(PROTO6-Pad8)") (class "Default")
      (node (ref "PROTO6") (pin "8") (pinfunction "8_8") (pintype "passive"))
    )
    (net (code "111") (name "unconnected-(PROTO7-Pad1)") (class "Default")
      (node (ref "PROTO7") (pin "1") (pinfunction "1_1") (pintype "passive"))
    )
    (net (code "112") (name "unconnected-(PROTO7-Pad2)") (class "Default")
      (node (ref "PROTO7") (pin "2") (pinfunction "2_2") (pintype "passive"))
    )
    (net (code "113") (name "unconnected-(PROTO7-Pad3)") (class "Default")
      (node (ref "PROTO7") (pin "3") (pinfunction "3_3") (pintype "passive"))
    )
    (net (code "114") (name "unconnected-(PROTO7-Pad4)") (class "Default")
      (node (ref "PROTO7") (pin "4") (pinfunction "4_4") (pintype "passive"))
    )
    (net (code "115") (name "unconnected-(PROTO7-Pad5)") (class "Default")
      (node (ref "PROTO7") (pin "5") (pinfunction "5_5") (pintype "passive"))
    )
    (net (code "116") (name "unconnected-(PROTO7-Pad6)") (class "Default")
      (node (ref "PROTO7") (pin "6") (pinfunction "6_6") (pintype "passive"))
    )
    (net (code "117") (name "unconnected-(PROTO7-Pad7)") (class "Default")
      (node (ref "PROTO7") (pin "7") (pinfunction "7_7") (pintype "passive"))
    )
    (net (code "118") (name "unconnected-(PROTO7-Pad8)") (class "Default")
      (node (ref "PROTO7") (pin "8") (pinfunction "8_8") (pintype "passive"))
    )
    (net (code "119") (name "unconnected-(PROTO8-Pad1)") (class "Default")
      (node (ref "PROTO8") (pin "1") (pinfunction "1_1") (pintype "passive"))
    )
    (net (code "120") (name "unconnected-(PROTO8-Pad2)") (class "Default")
      (node (ref "PROTO8") (pin "2") (pinfunction "2_2") (pintype "passive"))
    )
    (net (code "121") (name "unconnected-(PROTO8-Pad3)") (class "Default")
      (node (ref "PROTO8") (pin "3") (pinfunction "3_3") (pintype "passive"))
    )
    (net (code "122") (name "unconnected-(PROTO8-Pad4)") (class "Default")
      (node (ref "PROTO8") (pin "4") (pinfunction "4_4") (pintype "passive"))
    )
    (net (code "123") (name "unconnected-(PROTO8-Pad5)") (class "Default")
      (node (ref "PROTO8") (pin "5") (pinfunction "5_5") (pintype "passive"))
    )
    (net (code "124") (name "unconnected-(PROTO8-Pad6)") (class "Default")
      (node (ref "PROTO8") (pin "6") (pinfunction "6_6") (pintype "passive"))
    )
    (net (code "125") (name "unconnected-(PROTO8-Pad7)") (class "Default")
      (node (ref "PROTO8") (pin "7") (pinfunction "7_7") (pintype "passive"))
    )
    (net (code "126") (name "unconnected-(PROTO8-Pad8)") (class "Default")
      (node (ref "PROTO8") (pin "8") (pinfunction "8_8") (pintype "passive"))
    )
    (net (code "127") (name "unconnected-(PROTO9-Pad1)") (class "Default")
      (node (ref "PROTO9") (pin "1") (pinfunction "1_1") (pintype "passive"))
    )
    (net (code "128") (name "unconnected-(PROTO9-Pad2)") (class "Default")
      (node (ref "PROTO9") (pin "2") (pinfunction "2_2") (pintype "passive"))
    )
    (net (code "129") (name "unconnected-(PROTO9-Pad3)") (class "Default")
      (node (ref "PROTO9") (pin "3") (pinfunction "3_3") (pintype "passive"))
    )
    (net (code "130") (name "unconnected-(PROTO9-Pad4)") (class "Default")
      (node (ref "PROTO9") (pin "4") (pinfunction "4_4") (pintype "passive"))
    )
    (net (code "131") (name "unconnected-(PROTO9-Pad5)") (class "Default")
      (node (ref "PROTO9") (pin "5") (pinfunction "5_5") (pintype "passive"))
    )
    (net (code "132") (name "unconnected-(PROTO9-Pad6)") (class "Default")
      (node (ref "PROTO9") (pin "6") (pinfunction "6_6") (pintype "passive"))
    )
    (net (code "133") (name "unconnected-(PROTO9-Pad7)") (class "Default")
      (node (ref "PROTO9") (pin "7") (pinfunction "7_7") (pintype "passive"))
    )
    (net (code "134") (name "unconnected-(PROTO9-Pad8)") (class "Default")
      (node (ref "PROTO9") (pin "8") (pinfunction "8_8") (pintype "passive"))
    )
    (net (code "135") (name "unconnected-(PROTO10-Pad1)") (class "Default")
      (node (ref "PROTO10") (pin "1") (pinfunction "1_1") (pintype "passive"))
    )
    (net (code "136") (name "unconnected-(PROTO10-Pad2)") (class "Default")
      (node (ref "PROTO10") (pin "2") (pinfunction "2_2") (pintype "passive"))
    )
    (net (code "137") (name "unconnected-(PROTO10-Pad3)") (class "Default")
      (node (ref "PROTO10") (pin "3") (pinfunction "3_3") (pintype "passive"))
    )
    (net (code "138") (name "unconnected-(PROTO10-Pad4)") (class "Default")
      (node (ref "PROTO10") (pin "4") (pinfunction "4_4") (pintype "passive"))
    )
    (net (code "139") (name "unconnected-(PROTO10-Pad5)") (class "Default")
      (node (ref "PROTO10") (pin "5") (pinfunction "5_5") (pintype "passive"))
    )
    (net (code "140") (name "unconnected-(PROTO10-Pad6)") (class "Default")
      (node (ref "PROTO10") (pin "6") (pinfunction "6_6") (pintype "passive"))
    )
    (net (code "141") (name "unconnected-(PROTO10-Pad7)") (class "Default")
      (node (ref "PROTO10") (pin "7") (pinfunction "7_7") (pintype "passive"))
    )
    (net (code "142") (name "unconnected-(PROTO10-Pad8)") (class "Default")
      (node (ref "PROTO10") (pin "8") (pinfunction "8_8") (pintype "passive"))
    )
    (net (code "143") (name "unconnected-(PROTO11-Pad1)") (class "Default")
      (node (ref "PROTO11") (pin "1") (pinfunction "1_1") (pintype "passive"))
    )
    (net (code "144") (name "unconnected-(PROTO11-Pad2)") (class "Default")
      (node (ref "PROTO11") (pin "2") (pinfunction "2_2") (pintype "passive"))
    )
    (net (code "145") (name "unconnected-(PROTO11-Pad3)") (class "Default")
      (node (ref "PROTO11") (pin "3") (pinfunction "3_3") (pintype "passive"))
    )
    (net (code "146") (name "unconnected-(PROTO11-Pad4)") (class "Default")
      (node (ref "PROTO11") (pin "4") (pinfunction "4_4") (pintype "passive"))
    )
    (net (code "147") (name "unconnected-(PROTO11-Pad5)") (class "Default")
      (node (ref "PROTO11") (pin "5") (pinfunction "5_5") (pintype "passive"))
    )
    (net (code "148") (name "unconnected-(PROTO11-Pad6)") (class "Default")
      (node (ref "PROTO11") (pin "6") (pinfunction "6_6") (pintype "passive"))
    )
    (net (code "149") (name "unconnected-(PROTO11-Pad7)") (class "Default")
      (node (ref "PROTO11") (pin "7") (pinfunction "7_7") (pintype "passive"))
    )
    (net (code "150") (name "unconnected-(PROTO11-Pad8)") (class "Default")
      (node (ref "PROTO11") (pin "8") (pinfunction "8_8") (pintype "passive"))
    )
    (net (code "151") (name "unconnected-(PROTO12-Pad1)") (class "Default")
      (node (ref "PROTO12") (pin "1") (pinfunction "1_1") (pintype "passive"))
    )
    (net (code "152") (name "unconnected-(PROTO12-Pad2)") (class "Default")
      (node (ref "PROTO12") (pin "2") (pinfunction "2_2") (pintype "passive"))
    )
    (net (code "153") (name "unconnected-(PROTO12-Pad3)") (class "Default")
      (node (ref "PROTO12") (pin "3") (pinfunction "3_3") (pintype "passive"))
    )
    (net (code "154") (name "unconnected-(PROTO12-Pad4)") (class "Default")
      (node (ref "PROTO12") (pin "4") (pinfunction "4_4") (pintype "passive"))
    )
    (net (code "155") (name "unconnected-(PROTO12-Pad5)") (class "Default")
      (node (ref "PROTO12") (pin "5") (pinfunction "5_5") (pintype "passive"))
    )
    (net (code "156") (name "unconnected-(PROTO12-Pad6)") (class "Default")
      (node (ref "PROTO12") (pin "6") (pinfunction "6_6") (pintype "passive"))
    )
    (net (code "157") (name "unconnected-(PROTO12-Pad7)") (class "Default")
      (node (ref "PROTO12") (pin "7") (pinfunction "7_7") (pintype "passive"))
    )
    (net (code "158") (name "unconnected-(PROTO12-Pad8)") (class "Default")
      (node (ref "PROTO12") (pin "8") (pinfunction "8_8") (pintype "passive"))
    )
    (net (code "159") (name "unconnected-(PROTO13-Pad1)") (class "Default")
      (node (ref "PROTO13") (pin "1") (pinfunction "1_1") (pintype "passive"))
    )
    (net (code "160") (name "unconnected-(PROTO13-Pad2)") (class "Default")
      (node (ref "PROTO13") (pin "2") (pinfunction "2_2") (pintype "passive"))
    )
    (net (code "161") (name "unconnected-(PROTO13-Pad3)") (class "Default")
      (node (ref "PROTO13") (pin "3") (pinfunction "3_3") (pintype "passive"))
    )
    (net (code "162") (name "unconnected-(PROTO13-Pad4)") (class "Default")
      (node (ref "PROTO13") (pin "4") (pinfunction "4_4") (pintype "passive"))
    )
    (net (code "163") (name "unconnected-(PROTO13-Pad5)") (class "Default")
      (node (ref "PROTO13") (pin "5") (pinfunction "5_5") (pintype "passive"))
    )
    (net (code "164") (name "unconnected-(PROTO13-Pad6)") (class "Default")
      (node (ref "PROTO13") (pin "6") (pinfunction "6_6") (pintype "passive"))
    )
    (net (code "165") (name "unconnected-(PROTO13-Pad7)") (class "Default")
      (node (ref "PROTO13") (pin "7") (pinfunction "7_7") (pintype "passive"))
    )
    (net (code "166") (name "unconnected-(PROTO13-Pad8)") (class "Default")
      (node (ref "PROTO13") (pin "8") (pinfunction "8_8") (pintype "passive"))
    )
    (net (code "167") (name "unconnected-(PROTO14-Pad1)") (class "Default")
      (node (ref "PROTO14") (pin "1") (pinfunction "1_1") (pintype "passive"))
    )
    (net (code "168") (name "unconnected-(PROTO14-Pad2)") (class "Default")
      (node (ref "PROTO14") (pin "2") (pinfunction "2_2") (pintype "passive"))
    )
    (net (code "169") (name "unconnected-(PROTO14-Pad3)") (class "Default")
      (node (ref "PROTO14") (pin "3") (pinfunction "3_3") (pintype "passive"))
    )
    (net (code "170") (name "unconnected-(PROTO14-Pad4)") (class "Default")
      (node (ref "PROTO14") (pin "4") (pinfunction "4_4") (pintype "passive"))
    )
    (net (code "171") (name "unconnected-(PROTO14-Pad5)") (class "Default")
      (node (ref "PROTO14") (pin "5") (pinfunction "5_5") (pintype "passive"))
    )
    (net (code "172") (name "unconnected-(PROTO14-Pad6)") (class "Default")
      (node (ref "PROTO14") (pin "6") (pinfunction "6_6") (pintype "passive"))
    )
    (net (code "173") (name "unconnected-(PROTO14-Pad7)") (class "Default")
      (node (ref "PROTO14") (pin "7") (pinfunction "7_7") (pintype "passive"))
    )
    (net (code "174") (name "unconnected-(PROTO14-Pad8)") (class "Default")
      (node (ref "PROTO14") (pin "8") (pinfunction "8_8") (pintype "passive"))
    )
    (net (code "175") (name "unconnected-(U$2-PadGPIO0)") (class "Default")
      (node (ref "U$2") (pin "GPIO0") (pinfunction "GPIO0_GPIO0") (pintype "bidirectional"))
    )
    (net (code "176") (name "unconnected-(U$2-PadGPIO2)") (class "Default")
      (node (ref "U$2") (pin "GPIO2") (pinfunction "GPIO2_GPIO2") (pintype "bidirectional"))
    )
  )
)
